# Adafruit_TS3USB30_USB_1_to_2_Switch.net
KiCad netlist of a schematic drawn in EAGLE
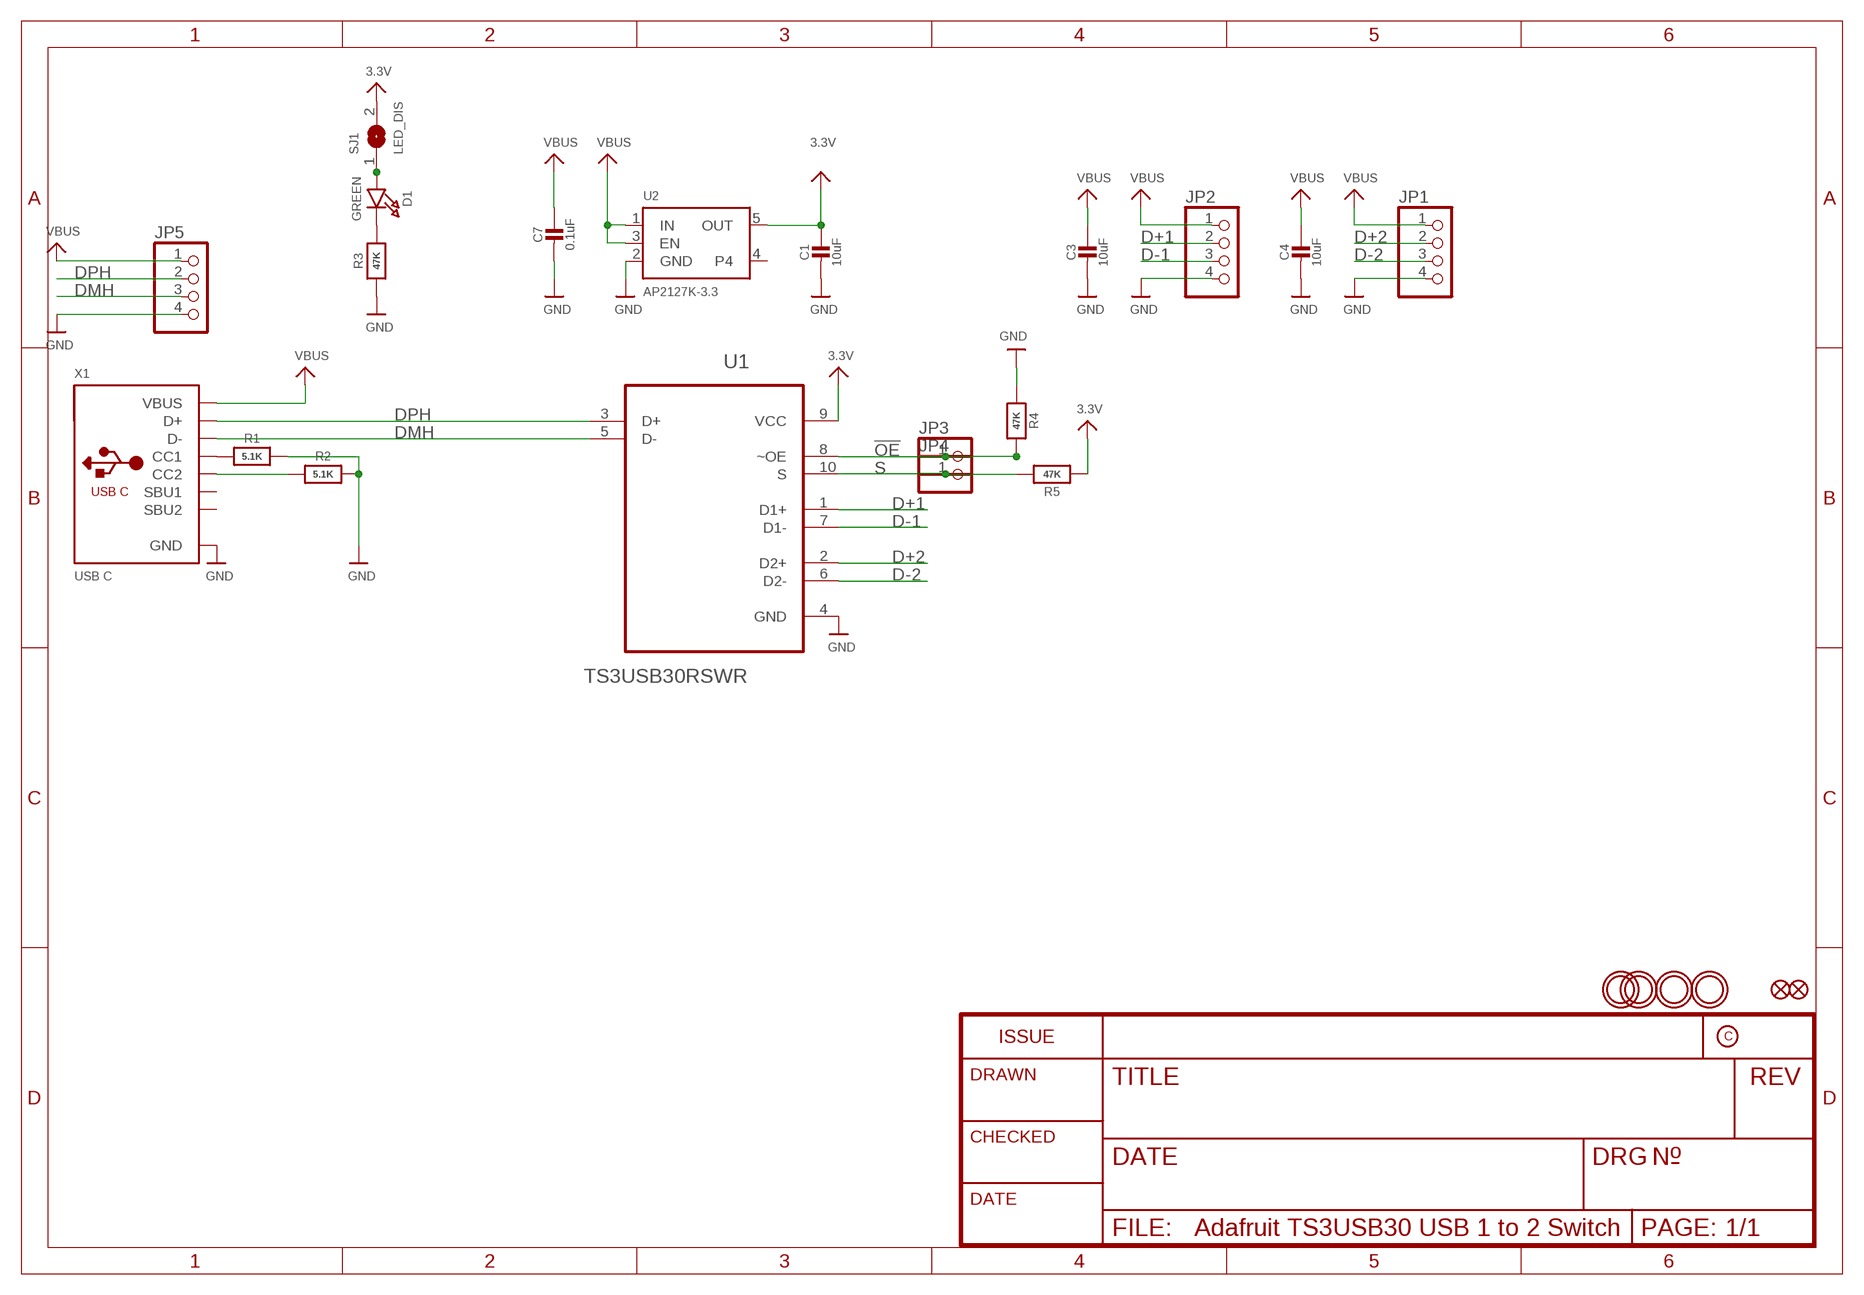
[diagram p0: schematic, sheet 1]

(export (version "E")
  (design (tool "Eeschema 10.0.6"))
  (components
    (comp (ref "C1")
      (value "10uF")
      (footprint "eagle-import:0805-NO")
      (libsource (lib "eagle-import") (part "CAP_CERAMIC0805-NOOUTLINE"))
    )
    (comp (ref "C3")
      (value "10uF")
      (footprint "eagle-import:0805-NO")
      (libsource (lib "eagle-import") (part "CAP_CERAMIC0805-NOOUTLINE"))
    )
    (comp (ref "C4")
      (value "10uF")
      (footprint "eagle-import:0805-NO")
      (libsource (lib "eagle-import") (part "CAP_CERAMIC0805-NOOUTLINE"))
    )
    (comp (ref "C7")
      (value "0.1uF")
      (footprint "eagle-import:0603-NO")
      (libsource (lib "eagle-import") (part "CAP_CERAMIC0603_NO"))
    )
    (comp (ref "D1")
      (value "GREEN")
      (footprint "eagle-import:CHIPLED_0603_NOOUTLINE")
      (libsource (lib "eagle-import") (part "LED0603_NOOUTLINE"))
    )
    (comp (ref "FID1")
      (value "FIDUCIAL_1MM")
      (footprint "eagle-import:FIDUCIAL_1MM")
      (libsource (lib "eagle-import") (part "FIDUCIAL_1MM"))
    )
    (comp (ref "FID2")
      (value "FIDUCIAL_1MM")
      (footprint "eagle-import:FIDUCIAL_1MM")
      (libsource (lib "eagle-import") (part "FIDUCIAL_1MM"))
    )
    (comp (ref "JP1")
      (value "HEADER-1X4ROUND")
      (footprint "eagle-import:1X04_ROUND")
      (libsource (lib "eagle-import") (part "HEADER-1X4ROUND"))
    )
    (comp (ref "JP2")
      (value "HEADER-1X4ROUND")
      (footprint "eagle-import:1X04_ROUND")
      (libsource (lib "eagle-import") (part "HEADER-1X4ROUND"))
    )
    (comp (ref "JP3")
      (value "HEADER-1X1ROUND_76MIL")
      (footprint "eagle-import:1X01_ROUND_76MIL")
      (libsource (lib "eagle-import") (part "HEADER-1X1ROUND_76MIL"))
    )
    (comp (ref "JP4")
      (value "HEADER-1X1ROUND_76MIL")
      (footprint "eagle-import:1X01_ROUND_76MIL")
      (libsource (lib "eagle-import") (part "HEADER-1X1ROUND_76MIL"))
    )
    (comp (ref "JP5")
      (value "HEADER-1X4ROUND")
      (footprint "eagle-import:1X04_ROUND")
      (libsource (lib "eagle-import") (part "HEADER-1X4ROUND"))
    )
    (comp (ref "R1")
      (value "5.1K")
      (footprint "eagle-import:0603-NO")
      (libsource (lib "eagle-import") (part "RESISTOR_0603_NOOUT"))
    )
    (comp (ref "R2")
      (value "5.1K")
      (footprint "eagle-import:0603-NO")
      (libsource (lib "eagle-import") (part "RESISTOR_0603_NOOUT"))
    )
    (comp (ref "R3")
      (value "47K")
      (footprint "eagle-import:0603-NO")
      (libsource (lib "eagle-import") (part "RESISTOR_0603_NOOUT"))
    )
    (comp (ref "R4")
      (value "47K")
      (footprint "eagle-import:0603-NO")
      (libsource (lib "eagle-import") (part "RESISTOR_0603_NOOUT"))
    )
    (comp (ref "R5")
      (value "47K")
      (footprint "eagle-import:0603-NO")
      (libsource (lib "eagle-import") (part "RESISTOR_0603_NOOUT"))
    )
    (comp (ref "SJ1")
      (value "LED_DIS")
      (footprint "eagle-import:SOLDERJUMPER_CLOSEDWIRE")
      (libsource (lib "eagle-import") (part "SOLDERJUMPERCLOSED"))
    )
    (comp (ref "U$23")
      (value "MOUNTINGHOLE2.5")
      (footprint "eagle-import:MOUNTINGHOLE_2.5_PLATED")
      (libsource (lib "eagle-import") (part "MOUNTINGHOLE2.5"))
    )
    (comp (ref "U$28")
      (value "MOUNTINGHOLE2.5")
      (footprint "eagle-import:MOUNTINGHOLE_2.5_PLATED")
      (libsource (lib "eagle-import") (part "MOUNTINGHOLE2.5"))
    )
    (comp (ref "U$29")
      (value "MOUNTINGHOLE2.5")
      (footprint "eagle-import:MOUNTINGHOLE_2.5_PLATED")
      (libsource (lib "eagle-import") (part "MOUNTINGHOLE2.5"))
    )
    (comp (ref "U$31")
      (value "MOUNTINGHOLE2.5")
      (footprint "eagle-import:MOUNTINGHOLE_2.5_PLATED")
      (libsource (lib "eagle-import") (part "MOUNTINGHOLE2.5"))
    )
    (comp (ref "U1")
      (value "TS3USB30RSWR")
      (footprint "eagle-import:10-UFQFN")
      (fields (field (name "DIGI-KEY_PART_NUMBER") "296-22547-2-ND") (field (name "MF") "Texas Instruments"))
      (libsource (lib "eagle-import") (part "TS3USB30RSWR"))
    )
    (comp (ref "U2")
      (value "AP2127K-3.3")
      (footprint "eagle-import:SOT23-5")
      (libsource (lib "eagle-import") (part "VREG_SOT23-5"))
    )
    (comp (ref "X1")
      (value "USB C")
      (footprint "eagle-import:USB_C_CUSB31-CFM2AX-01-X")
      (libsource (lib "eagle-import") (part "USB_C"))
    )
  )
  (nets
    (net (code "1") (name "/D+1") (class "Default")
      (node (ref "JP2") (pin "2") (pinfunction "2_2") (pintype "passive"))
      (node (ref "U1") (pin "1") (pinfunction "D1+_1") (pintype "bidirectional"))
    )
    (net (code "2") (name "/D+2") (class "Default")
      (node (ref "JP1") (pin "2") (pinfunction "2_2") (pintype "passive"))
      (node (ref "U1") (pin "2") (pinfunction "D2+_2") (pintype "bidirectional"))
    )
    (net (code "3") (name "/D-1") (class "Default")
      (node (ref "JP2") (pin "3") (pinfunction "3_3") (pintype "passive"))
      (node (ref "U1") (pin "7") (pinfunction "D1-_7") (pintype "bidirectional"))
    )
    (net (code "4") (name "/D-2") (class "Default")
      (node (ref "JP1") (pin "3") (pinfunction "3_3") (pintype "passive"))
      (node (ref "U1") (pin "6") (pinfunction "D2-_6") (pintype "bidirectional"))
    )
    (net (code "5") (name "/DMH") (class "Default")
      (node (ref "JP5") (pin "3") (pinfunction "3_3") (pintype "passive"))
      (node (ref "U1") (pin "5") (pinfunction "D-_5") (pintype "bidirectional"))
      (node (ref "X1") (pin "A7") (pinfunction "D-_A7") (pintype "bidirectional"))
      (node (ref "X1") (pin "B7") (pinfunction "D-_B7") (pintype "bidirectional"))
    )
    (net (code "6") (name "/DPH") (class "Default")
      (node (ref "JP5") (pin "2") (pinfunction "2_2") (pintype "passive"))
      (node (ref "U1") (pin "3") (pinfunction "D+_3") (pintype "bidirectional"))
      (node (ref "X1") (pin "A6") (pinfunction "D+_A6") (pintype "bidirectional"))
      (node (ref "X1") (pin "B6") (pinfunction "D+_B6") (pintype "bidirectional"))
    )
    (net (code "7") (name "/S") (class "Default")
      (node (ref "JP4") (pin "1") (pinfunction "1_1") (pintype "passive"))
      (node (ref "R5") (pin "2") (pinfunction "2_2") (pintype "passive"))
      (node (ref "U1") (pin "10") (pinfunction "S_10") (pintype "input"))
    )
    (net (code "8") (name "/~{OE}") (class "Default")
      (node (ref "JP3") (pin "1") (pinfunction "1_1") (pintype "passive"))
      (node (ref "R4") (pin "2") (pinfunction "2_2") (pintype "passive"))
      (node (ref "U1") (pin "8") (pinfunction "~{OE}_8") (pintype "input"))
    )
    (net (code "9") (name "3.3V") (class "Default")
      (node (ref "C1") (pin "1") (pinfunction "1_1") (pintype "passive"))
      (node (ref "R5") (pin "1") (pinfunction "1_1") (pintype "passive"))
      (node (ref "SJ1") (pin "2") (pinfunction "2_2") (pintype "passive"))
      (node (ref "U1") (pin "9") (pinfunction "VCC_9") (pintype "power_in"))
      (node (ref "U2") (pin "5") (pinfunction "OUT_5") (pintype "power_in"))
    )
    (net (code "10") (name "GND") (class "Default")
      (node (ref "C1") (pin "2") (pinfunction "2_2") (pintype "passive"))
      (node (ref "C3") (pin "2") (pinfunction "2_2") (pintype "passive"))
      (node (ref "C4") (pin "2") (pinfunction "2_2") (pintype "passive"))
      (node (ref "C7") (pin "2") (pinfunction "2_2") (pintype "passive"))
      (node (ref "JP1") (pin "4") (pinfunction "4_4") (pintype "passive"))
      (node (ref "JP2") (pin "4") (pinfunction "4_4") (pintype "passive"))
      (node (ref "JP5") (pin "4") (pinfunction "4_4") (pintype "passive"))
      (node (ref "R1") (pin "2") (pinfunction "2_2") (pintype "passive"))
      (node (ref "R2") (pin "2") (pinfunction "2_2") (pintype "passive"))
      (node (ref "R3") (pin "1") (pinfunction "1_1") (pintype "passive"))
      (node (ref "R4") (pin "1") (pinfunction "1_1") (pintype "passive"))
      (node (ref "U1") (pin "4") (pinfunction "GND_4") (pintype "passive"))
      (node (ref "U2") (pin "2") (pinfunction "GND_2") (pintype "power_in"))
      (node (ref "X1") (pin "A1B12") (pinfunction "GND_A1B12") (pintype "power_in"))
      (node (ref "X1") (pin "B1A12") (pinfunction "GND_B1A12") (pintype "power_in"))
    )
    (net (code "11") (name "Net-(D1-PadA)") (class "Default")
      (node (ref "D1") (pin "A") (pinfunction "A_A") (pintype "passive"))
      (node (ref "SJ1") (pin "1") (pinfunction "1_1") (pintype "passive"))
    )
    (net (code "12") (name "Net-(D1-PadC)") (class "Default")
      (node (ref "D1") (pin "C") (pinfunction "C_C") (pintype "passive"))
      (node (ref "R3") (pin "2") (pinfunction "2_2") (pintype "passive"))
    )
    (net (code "13") (name "Net-(X1-CC1)") (class "Default")
      (node (ref "R1") (pin "1") (pinfunction "1_1") (pintype "passive"))
      (node (ref "X1") (pin "A5") (pinfunction "CC1_A5") (pintype "bidirectional"))
    )
    (net (code "14") (name "Net-(X1-CC2)") (class "Default")
      (node (ref "R2") (pin "1") (pinfunction "1_1") (pintype "passive"))
      (node (ref "X1") (pin "B5") (pinfunction "CC2_B5") (pintype "bidirectional"))
    )
    (net (code "15") (name "VBUS") (class "Default")
      (node (ref "C3") (pin "1") (pinfunction "1_1") (pintype "passive"))
      (node (ref "C4") (pin "1") (pinfunction "1_1") (pintype "passive"))
      (node (ref "C7") (pin "1") (pinfunction "1_1") (pintype "passive"))
      (node (ref "JP1") (pin "1") (pinfunction "1_1") (pintype "passive"))
      (node (ref "JP2") (pin "1") (pinfunction "1_1") (pintype "passive"))
      (node (ref "JP5") (pin "1") (pinfunction "1_1") (pintype "passive"))
      (node (ref "U2") (pin "1") (pinfunction "IN_1") (pintype "power_in"))
      (node (ref "U2") (pin "3") (pinfunction "EN_3") (pintype "input"))
      (node (ref "X1") (pin "A4B9") (pinfunction "VBUS_A4B9") (pintype "power_in"))
      (node (ref "X1") (pin "B4A9") (pinfunction "VBUS_B4A9") (pintype "power_in"))
    )
    (net (code "16") (name "unconnected-(U2-P4-Pad4)") (class "Default")
      (node (ref "U2") (pin "4") (pinfunction "P4_4") (pintype "bidirectional"))
    )
    (net (code "17") (name "unconnected-(X1-SBU1-PadA8)") (class "Default")
      (node (ref "X1") (pin "A8") (pinfunction "SBU1_A8") (pintype "bidirectional"))
    )
    (net (code "18") (name "unconnected-(X1-SBU2-PadB8)") (class "Default")
      (node (ref "X1") (pin "B8") (pinfunction "SBU2_B8") (pintype "bidirectional"))
    )
  )
)
